# UPCNSL-ABS-PVC-TOP.net
KiCad netlist of a schematic drawn in Altium Designer
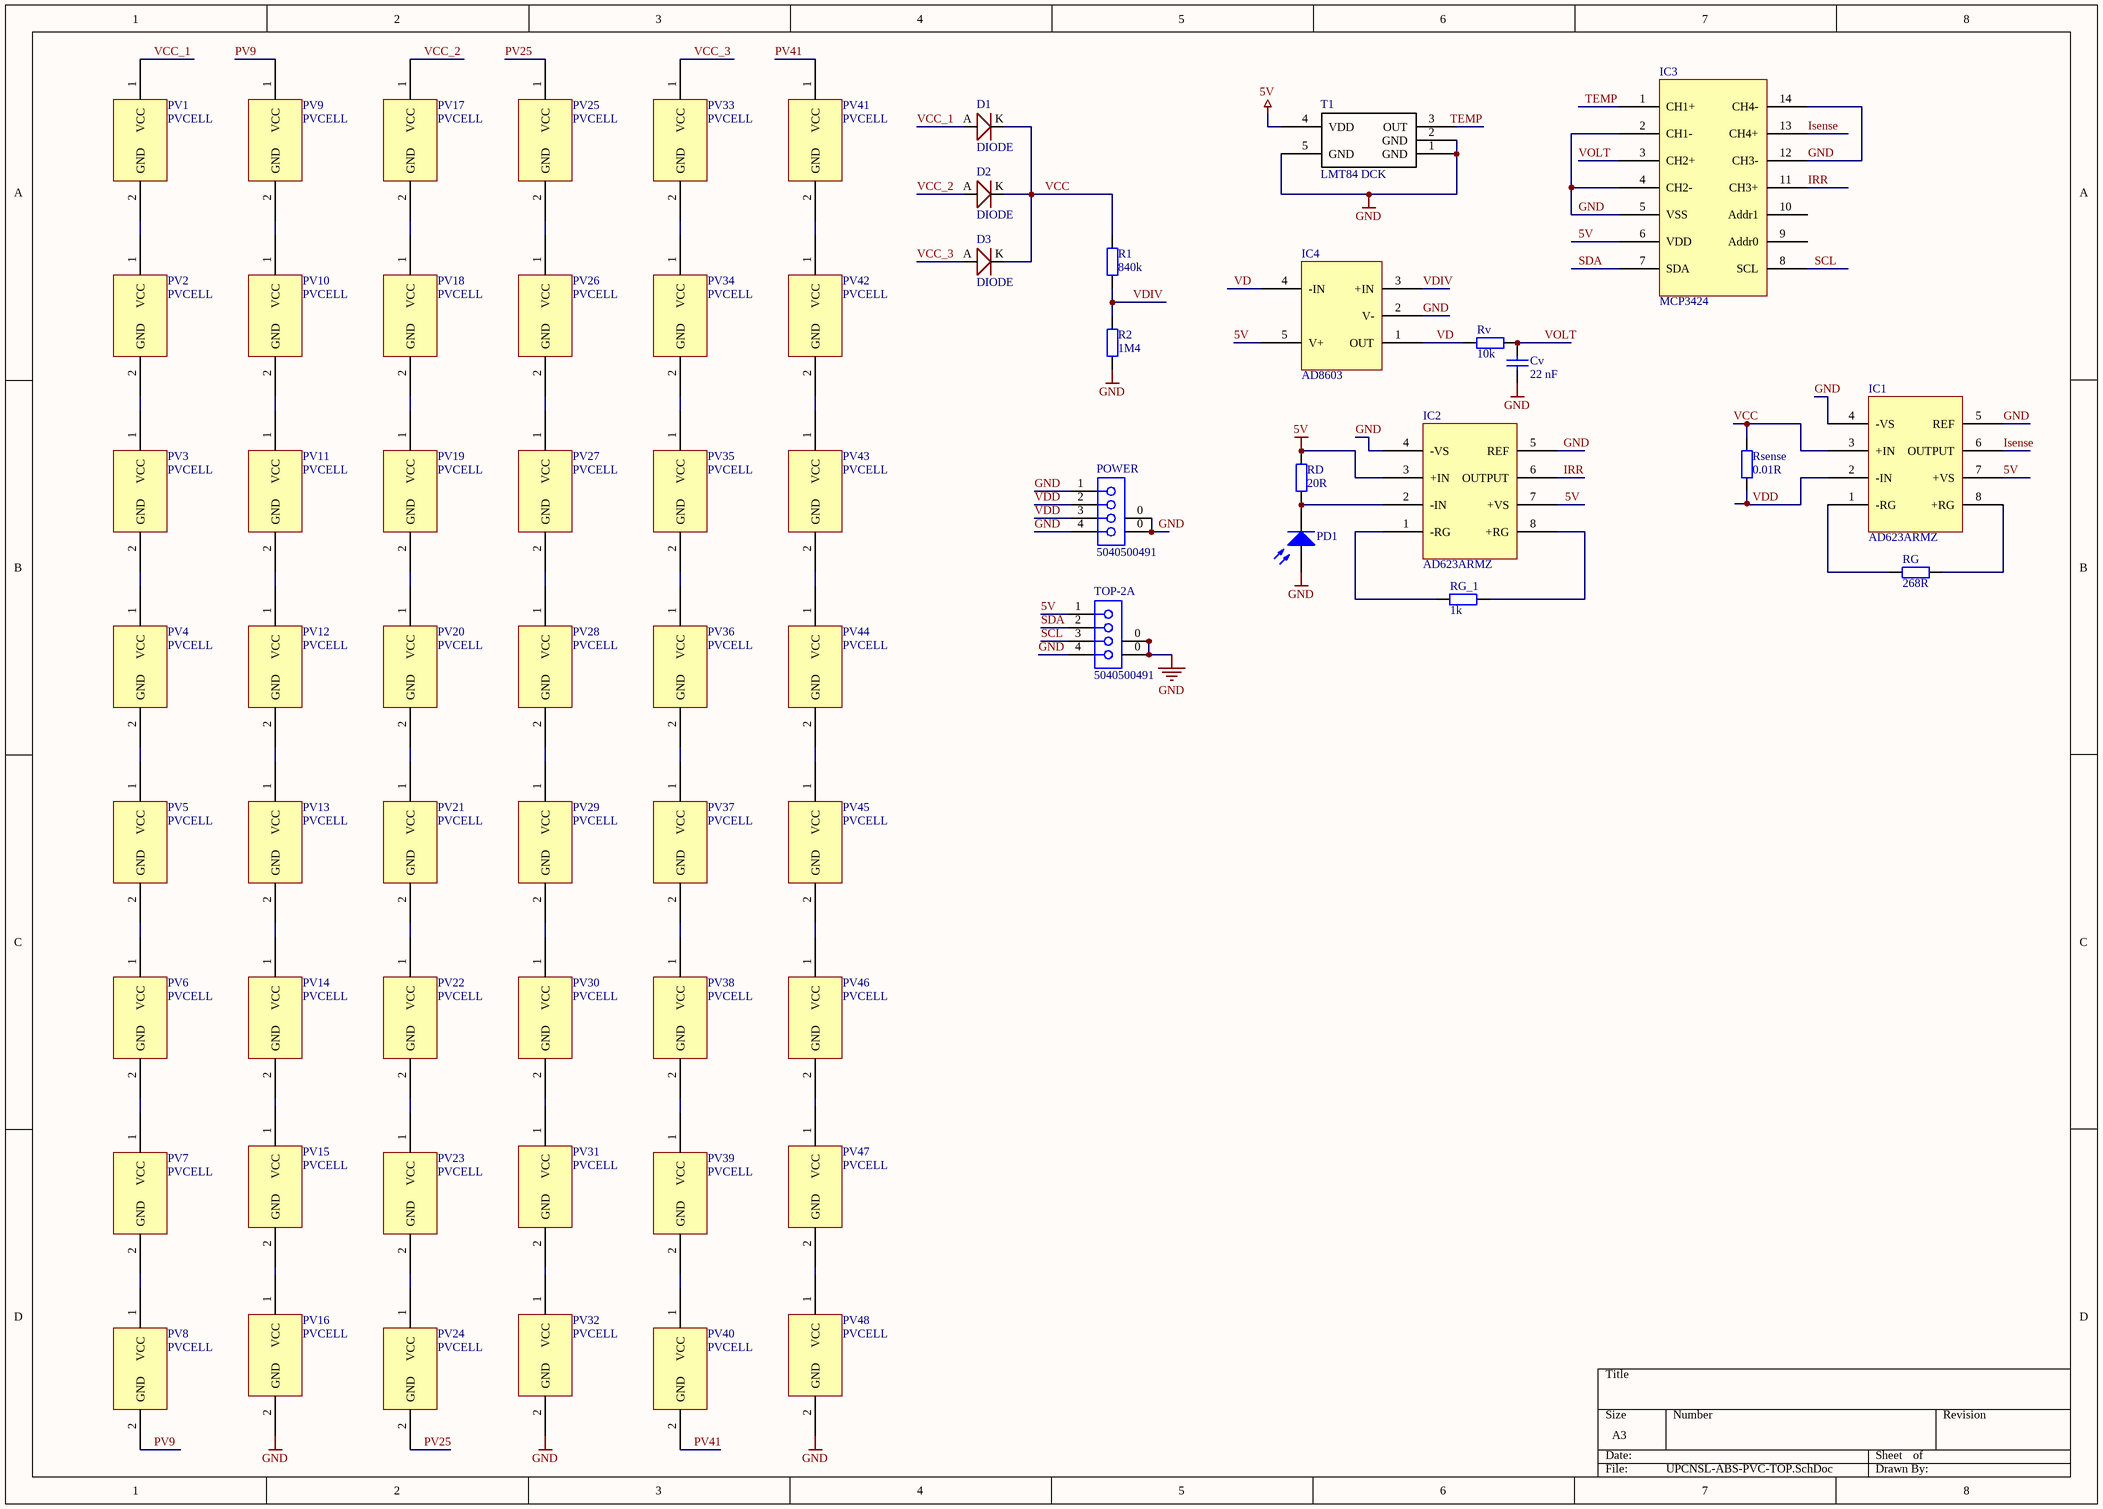
[diagram p0: UPCNSL-ABS-PVC-TOP.SchDoc]

(export (version "E")
  (design (tool "Eeschema 10.0.6"))
  (components
    (comp (ref "Cv")
      (value "22 nF")
      (footprint "CAP0603")
      (description "Capacitor")
      (fields (field (name "Comment") "CAP0603"))
      (libsource (lib "UPCNSL-ABS-FLS-ARD_v1.2") (part "CAP0603"))
    )
    (comp (ref "D1")
      (value "DIODE")
      (footprint "(Schottky diode) SODFL160X70-2N")
      (libsource (lib "UPCNSL-ABS-FLS-ARD_v1.2") (part "DIODE"))
    )
    (comp (ref "D2")
      (value "DIODE")
      (footprint "(Schottky diode) SODFL160X70-2N")
      (libsource (lib "UPCNSL-ABS-FLS-ARD_v1.2") (part "DIODE"))
    )
    (comp (ref "D3")
      (value "DIODE")
      (footprint "(Schottky diode) SODFL160X70-2N")
      (libsource (lib "UPCNSL-ABS-FLS-ARD_v1.2") (part "DIODE"))
    )
    (comp (ref "IC1")
      (value "AD623ARMZ")
      (footprint "AD623ARMZ")
      (libsource (lib "UPCNSL-ABS-FLS-PVC") (part "AD623ARMZ"))
    )
    (comp (ref "IC2")
      (value "AD623ARMZ")
      (footprint "AD623ARMZ")
      (libsource (lib "UPCNSL-ABS-FLS-PVC") (part "AD623ARMZ"))
    )
    (comp (ref "IC3")
      (value "MCP3424")
      (footprint "MCP3424")
      (description "18-Bit, Multi-Channel ΔΣ Analog-to-Digital Converter with  I2C")
      (libsource (lib "UPCNSL-ABS-FLS-PVC") (part "MCP3424"))
    )
    (comp (ref "IC4")
      (value "AD8603")
      (footprint "AD8603")
      (libsource (lib "UPCNSL-ABS-FLS-PVC") (part "AD8603"))
    )
    (comp (ref "PD1")
      (value "Photo Sen")
      (footprint "C0805")
      (description "Photosensitive Diode")
      (fields (field (name "PUBLISHER") "Altium Limited"))
      (libsource (lib "Miscellaneous Devices") (part "Photo Sen"))
    )
    (comp (ref "POWER")
      (value "5040500491")
      (footprint "5040500491")
      (libsource (lib "3CAT_Connectors") (part "MOLEX_5040500491"))
    )
    (comp (ref "PV1")
      (value "PVCELL")
      (footprint "PV CELLS")
      (description "IXYS KXOB22-12X1L-ND")
      (libsource (lib "UPCNSL-ABS-FLS-PVC") (part "PVCELLS"))
    )
    (comp (ref "PV2")
      (value "PVCELL")
      (footprint "PV CELLS")
      (description "IXYS KXOB22-12X1L-ND")
      (libsource (lib "UPCNSL-ABS-FLS-PVC") (part "PVCELLS"))
    )
    (comp (ref "PV3")
      (value "PVCELL")
      (footprint "PV CELLS")
      (description "IXYS KXOB22-12X1L-ND")
      (libsource (lib "UPCNSL-ABS-FLS-PVC") (part "PVCELLS"))
    )
    (comp (ref "PV4")
      (value "PVCELL")
      (footprint "PV CELLS")
      (description "IXYS KXOB22-12X1L-ND")
      (libsource (lib "UPCNSL-ABS-FLS-PVC") (part "PVCELLS"))
    )
    (comp (ref "PV5")
      (value "PVCELL")
      (footprint "PV CELLS")
      (description "IXYS KXOB22-12X1L-ND")
      (libsource (lib "UPCNSL-ABS-FLS-PVC") (part "PVCELLS"))
    )
    (comp (ref "PV6")
      (value "PVCELL")
      (footprint "PV CELLS")
      (description "IXYS KXOB22-12X1L-ND")
      (libsource (lib "UPCNSL-ABS-FLS-PVC") (part "PVCELLS"))
    )
    (comp (ref "PV7")
      (value "PVCELL")
      (footprint "PV CELLS")
      (description "IXYS KXOB22-12X1L-ND")
      (libsource (lib "UPCNSL-ABS-FLS-PVC") (part "PVCELLS"))
    )
    (comp (ref "PV8")
      (value "PVCELL")
      (footprint "PV CELLS")
      (description "IXYS KXOB22-12X1L-ND")
      (libsource (lib "UPCNSL-ABS-FLS-PVC") (part "PVCELLS"))
    )
    (comp (ref "PV9")
      (value "PVCELL")
      (footprint "PV CELLS")
      (description "IXYS KXOB22-12X1L-ND")
      (libsource (lib "UPCNSL-ABS-FLS-PVC") (part "PVCELLS"))
    )
    (comp (ref "PV10")
      (value "PVCELL")
      (footprint "PV CELLS")
      (description "IXYS KXOB22-12X1L-ND")
      (libsource (lib "UPCNSL-ABS-FLS-PVC") (part "PVCELLS"))
    )
    (comp (ref "PV11")
      (value "PVCELL")
      (footprint "PV CELLS")
      (description "IXYS KXOB22-12X1L-ND")
      (libsource (lib "UPCNSL-ABS-FLS-PVC") (part "PVCELLS"))
    )
    (comp (ref "PV12")
      (value "PVCELL")
      (footprint "PV CELLS")
      (description "IXYS KXOB22-12X1L-ND")
      (libsource (lib "UPCNSL-ABS-FLS-PVC") (part "PVCELLS"))
    )
    (comp (ref "PV13")
      (value "PVCELL")
      (footprint "PV CELLS")
      (description "IXYS KXOB22-12X1L-ND")
      (libsource (lib "UPCNSL-ABS-FLS-PVC") (part "PVCELLS"))
    )
    (comp (ref "PV14")
      (value "PVCELL")
      (footprint "PV CELLS")
      (description "IXYS KXOB22-12X1L-ND")
      (libsource (lib "UPCNSL-ABS-FLS-PVC") (part "PVCELLS"))
    )
    (comp (ref "PV15")
      (value "PVCELL")
      (footprint "PV CELLS")
      (description "IXYS KXOB22-12X1L-ND")
      (libsource (lib "UPCNSL-ABS-FLS-PVC") (part "PVCELLS"))
    )
    (comp (ref "PV16")
      (value "PVCELL")
      (footprint "PV CELLS")
      (description "IXYS KXOB22-12X1L-ND")
      (libsource (lib "UPCNSL-ABS-FLS-PVC") (part "PVCELLS"))
    )
    (comp (ref "PV17")
      (value "PVCELL")
      (footprint "PV CELLS")
      (description "IXYS KXOB22-12X1L-ND")
      (libsource (lib "UPCNSL-ABS-FLS-PVC") (part "PVCELLS"))
    )
    (comp (ref "PV18")
      (value "PVCELL")
      (footprint "PV CELLS")
      (description "IXYS KXOB22-12X1L-ND")
      (libsource (lib "UPCNSL-ABS-FLS-PVC") (part "PVCELLS"))
    )
    (comp (ref "PV19")
      (value "PVCELL")
      (footprint "PV CELLS")
      (description "IXYS KXOB22-12X1L-ND")
      (libsource (lib "UPCNSL-ABS-FLS-PVC") (part "PVCELLS"))
    )
    (comp (ref "PV20")
      (value "PVCELL")
      (footprint "PV CELLS")
      (description "IXYS KXOB22-12X1L-ND")
      (libsource (lib "UPCNSL-ABS-FLS-PVC") (part "PVCELLS"))
    )
    (comp (ref "PV21")
      (value "PVCELL")
      (footprint "PV CELLS")
      (description "IXYS KXOB22-12X1L-ND")
      (libsource (lib "UPCNSL-ABS-FLS-PVC") (part "PVCELLS"))
    )
    (comp (ref "PV22")
      (value "PVCELL")
      (footprint "PV CELLS")
      (description "IXYS KXOB22-12X1L-ND")
      (libsource (lib "UPCNSL-ABS-FLS-PVC") (part "PVCELLS"))
    )
    (comp (ref "PV23")
      (value "PVCELL")
      (footprint "PV CELLS")
      (description "IXYS KXOB22-12X1L-ND")
      (libsource (lib "UPCNSL-ABS-FLS-PVC") (part "PVCELLS"))
    )
    (comp (ref "PV24")
      (value "PVCELL")
      (footprint "PV CELLS")
      (description "IXYS KXOB22-12X1L-ND")
      (libsource (lib "UPCNSL-ABS-FLS-PVC") (part "PVCELLS"))
    )
    (comp (ref "PV25")
      (value "PVCELL")
      (footprint "PV CELLS")
      (description "IXYS KXOB22-12X1L-ND")
      (libsource (lib "UPCNSL-ABS-FLS-PVC") (part "PVCELLS"))
    )
    (comp (ref "PV26")
      (value "PVCELL")
      (footprint "PV CELLS")
      (description "IXYS KXOB22-12X1L-ND")
      (libsource (lib "UPCNSL-ABS-FLS-PVC") (part "PVCELLS"))
    )
    (comp (ref "PV27")
      (value "PVCELL")
      (footprint "PV CELLS")
      (description "IXYS KXOB22-12X1L-ND")
      (libsource (lib "UPCNSL-ABS-FLS-PVC") (part "PVCELLS"))
    )
    (comp (ref "PV28")
      (value "PVCELL")
      (footprint "PV CELLS")
      (description "IXYS KXOB22-12X1L-ND")
      (libsource (lib "UPCNSL-ABS-FLS-PVC") (part "PVCELLS"))
    )
    (comp (ref "PV29")
      (value "PVCELL")
      (footprint "PV CELLS")
      (description "IXYS KXOB22-12X1L-ND")
      (libsource (lib "UPCNSL-ABS-FLS-PVC") (part "PVCELLS"))
    )
    (comp (ref "PV30")
      (value "PVCELL")
      (footprint "PV CELLS")
      (description "IXYS KXOB22-12X1L-ND")
      (libsource (lib "UPCNSL-ABS-FLS-PVC") (part "PVCELLS"))
    )
    (comp (ref "PV31")
      (value "PVCELL")
      (footprint "PV CELLS")
      (description "IXYS KXOB22-12X1L-ND")
      (libsource (lib "UPCNSL-ABS-FLS-PVC") (part "PVCELLS"))
    )
    (comp (ref "PV32")
      (value "PVCELL")
      (footprint "PV CELLS")
      (description "IXYS KXOB22-12X1L-ND")
      (libsource (lib "UPCNSL-ABS-FLS-PVC") (part "PVCELLS"))
    )
    (comp (ref "PV33")
      (value "PVCELL")
      (footprint "PV CELLS")
      (description "IXYS KXOB22-12X1L-ND")
      (libsource (lib "UPCNSL-ABS-FLS-PVC") (part "PVCELLS"))
    )
    (comp (ref "PV34")
      (value "PVCELL")
      (footprint "PV CELLS")
      (description "IXYS KXOB22-12X1L-ND")
      (libsource (lib "UPCNSL-ABS-FLS-PVC") (part "PVCELLS"))
    )
    (comp (ref "PV35")
      (value "PVCELL")
      (footprint "PV CELLS")
      (description "IXYS KXOB22-12X1L-ND")
      (libsource (lib "UPCNSL-ABS-FLS-PVC") (part "PVCELLS"))
    )
    (comp (ref "PV36")
      (value "PVCELL")
      (footprint "PV CELLS")
      (description "IXYS KXOB22-12X1L-ND")
      (libsource (lib "UPCNSL-ABS-FLS-PVC") (part "PVCELLS"))
    )
    (comp (ref "PV37")
      (value "PVCELL")
      (footprint "PV CELLS")
      (description "IXYS KXOB22-12X1L-ND")
      (libsource (lib "UPCNSL-ABS-FLS-PVC") (part "PVCELLS"))
    )
    (comp (ref "PV38")
      (value "PVCELL")
      (footprint "PV CELLS")
      (description "IXYS KXOB22-12X1L-ND")
      (libsource (lib "UPCNSL-ABS-FLS-PVC") (part "PVCELLS"))
    )
    (comp (ref "PV39")
      (value "PVCELL")
      (footprint "PV CELLS")
      (description "IXYS KXOB22-12X1L-ND")
      (libsource (lib "UPCNSL-ABS-FLS-PVC") (part "PVCELLS"))
    )
    (comp (ref "PV40")
      (value "PVCELL")
      (footprint "PV CELLS")
      (description "IXYS KXOB22-12X1L-ND")
      (libsource (lib "UPCNSL-ABS-FLS-PVC") (part "PVCELLS"))
    )
    (comp (ref "PV41")
      (value "PVCELL")
      (footprint "PV CELLS")
      (description "IXYS KXOB22-12X1L-ND")
      (libsource (lib "UPCNSL-ABS-FLS-PVC") (part "PVCELLS"))
    )
    (comp (ref "PV42")
      (value "PVCELL")
      (footprint "PV CELLS")
      (description "IXYS KXOB22-12X1L-ND")
      (libsource (lib "UPCNSL-ABS-FLS-PVC") (part "PVCELLS"))
    )
    (comp (ref "PV43")
      (value "PVCELL")
      (footprint "PV CELLS")
      (description "IXYS KXOB22-12X1L-ND")
      (libsource (lib "UPCNSL-ABS-FLS-PVC") (part "PVCELLS"))
    )
    (comp (ref "PV44")
      (value "PVCELL")
      (footprint "PV CELLS")
      (description "IXYS KXOB22-12X1L-ND")
      (libsource (lib "UPCNSL-ABS-FLS-PVC") (part "PVCELLS"))
    )
    (comp (ref "PV45")
      (value "PVCELL")
      (footprint "PV CELLS")
      (description "IXYS KXOB22-12X1L-ND")
      (libsource (lib "UPCNSL-ABS-FLS-PVC") (part "PVCELLS"))
    )
    (comp (ref "PV46")
      (value "PVCELL")
      (footprint "PV CELLS")
      (description "IXYS KXOB22-12X1L-ND")
      (libsource (lib "UPCNSL-ABS-FLS-PVC") (part "PVCELLS"))
    )
    (comp (ref "PV47")
      (value "PVCELL")
      (footprint "PV CELLS")
      (description "IXYS KXOB22-12X1L-ND")
      (libsource (lib "UPCNSL-ABS-FLS-PVC") (part "PVCELLS"))
    )
    (comp (ref "PV48")
      (value "PVCELL")
      (footprint "PV CELLS")
      (description "IXYS KXOB22-12X1L-ND")
      (libsource (lib "UPCNSL-ABS-FLS-PVC") (part "PVCELLS"))
    )
    (comp (ref "R1")
      (value "840k")
      (footprint "RES0603")
      (description "Resistor")
      (fields (field (name "Comment") "RES0603"))
      (libsource (lib "UPCNSL-ABS-FLS-ARD_v1.2") (part "RES0603"))
    )
    (comp (ref "R2")
      (value "1M4")
      (footprint "RES0603")
      (description "Resistor")
      (fields (field (name "Comment") "RES0603"))
      (libsource (lib "UPCNSL-ABS-FLS-ARD_v1.2") (part "RES0603"))
    )
    (comp (ref "RD")
      (value "20R")
      (footprint "RES0603")
      (description "Resistor")
      (fields (field (name "Comment") "RES0603"))
      (libsource (lib "UPCNSL-ABS-FLS-ARD_v1.2") (part "RES0603"))
    )
    (comp (ref "RG")
      (value "268R")
      (footprint "RES0603")
      (description "Resistor")
      (fields (field (name "Comment") "RES0603"))
      (libsource (lib "") (part "RES0603_1"))
    )
    (comp (ref "RG_1")
      (value "1k")
      (footprint "RES0603")
      (description "Resistor")
      (fields (field (name "Comment") "RES0603"))
      (libsource (lib "") (part "RES0603_1"))
    )
    (comp (ref "Rsense")
      (value "0.01R")
      (footprint "RES0603")
      (description "Resistor")
      (fields (field (name "Comment") "RES0603"))
      (libsource (lib "UPCNSL-ABS-FLS-ARD_v1.2") (part "RES0603"))
    )
    (comp (ref "Rv")
      (value "10k")
      (footprint "RES0603")
      (description "Resistor")
      (fields (field (name "Comment") "RES0603"))
      (libsource (lib "") (part "RES0603_1"))
    )
    (comp (ref "T1")
      (value "LMT84 DCK")
      (footprint "DCK/SOT65P210X110-5N")
      (libsource (lib "UPCNSL-ABS-FLS-PVC") (part "LMT84 DCK"))
    )
    (comp (ref "TOP-2A")
      (value "5040500491")
      (footprint "5040500491")
      (libsource (lib "3CAT_Connectors") (part "MOLEX_5040500491"))
    )
  )
  (nets
    (net (code "1") (name "/IRR") (class "Default")
      (node (ref "IC2") (pin "6") (pinfunction "OUTPUT_6") (pintype "passive"))
      (node (ref "IC3") (pin "11") (pinfunction "CH3+_11") (pintype "passive"))
    )
    (net (code "2") (name "/Isense") (class "Default")
      (node (ref "IC1") (pin "6") (pinfunction "OUTPUT_6") (pintype "passive"))
      (node (ref "IC3") (pin "13") (pinfunction "CH4+_13") (pintype "passive"))
    )
    (net (code "3") (name "/PV9") (class "Default")
      (node (ref "PV8") (pin "2") (pinfunction "GND_2") (pintype "passive"))
      (node (ref "PV9") (pin "1") (pinfunction "VCC_1") (pintype "passive"))
    )
    (net (code "4") (name "/PV25") (class "Default")
      (node (ref "PV24") (pin "2") (pinfunction "GND_2") (pintype "passive"))
      (node (ref "PV25") (pin "1") (pinfunction "VCC_1") (pintype "passive"))
    )
    (net (code "5") (name "/PV41") (class "Default")
      (node (ref "PV40") (pin "2") (pinfunction "GND_2") (pintype "passive"))
      (node (ref "PV41") (pin "1") (pinfunction "VCC_1") (pintype "passive"))
    )
    (net (code "6") (name "/SCL") (class "Default")
      (node (ref "IC3") (pin "8") (pinfunction "SCL_8") (pintype "passive"))
      (node (ref "TOP-2A") (pin "3") (pinfunction "3_3") (pintype "passive"))
    )
    (net (code "7") (name "/SDA") (class "Default")
      (node (ref "IC3") (pin "7") (pinfunction "SDA_7") (pintype "passive"))
      (node (ref "TOP-2A") (pin "2") (pinfunction "2_2") (pintype "passive"))
    )
    (net (code "8") (name "/TEMP") (class "Default")
      (node (ref "IC3") (pin "1") (pinfunction "CH1+_1") (pintype "passive"))
    )
    (net (code "9") (name "/VCC") (class "Default")
      (node (ref "D1") (pin "K") (pinfunction "K_K") (pintype "passive"))
      (node (ref "D2") (pin "K") (pinfunction "K_K") (pintype "passive"))
      (node (ref "D3") (pin "K") (pinfunction "K_K") (pintype "passive"))
      (node (ref "IC1") (pin "3") (pinfunction "+IN_3") (pintype "passive"))
      (node (ref "R1") (pin "2") (pinfunction "2_2") (pintype "passive"))
      (node (ref "Rsense") (pin "2") (pinfunction "2_2") (pintype "passive"))
    )
    (net (code "10") (name "/VCC_1") (class "Default")
      (node (ref "D1") (pin "A") (pinfunction "A_A") (pintype "passive"))
      (node (ref "PV1") (pin "1") (pinfunction "VCC_1") (pintype "passive"))
    )
    (net (code "11") (name "/VCC_2") (class "Default")
      (node (ref "D2") (pin "A") (pinfunction "A_A") (pintype "passive"))
      (node (ref "PV17") (pin "1") (pinfunction "VCC_1") (pintype "passive"))
    )
    (net (code "12") (name "/VCC_3") (class "Default")
      (node (ref "D3") (pin "A") (pinfunction "A_A") (pintype "passive"))
      (node (ref "PV33") (pin "1") (pinfunction "VCC_1") (pintype "passive"))
    )
    (net (code "13") (name "/VD") (class "Default")
      (node (ref "IC4") (pin "1") (pinfunction "OUT_1") (pintype "passive"))
      (node (ref "IC4") (pin "4") (pinfunction "-IN_4") (pintype "passive"))
      (node (ref "Rv") (pin "1") (pinfunction "1_1") (pintype "passive"))
    )
    (net (code "14") (name "/VDD") (class "Default")
      (node (ref "IC1") (pin "2") (pinfunction "-IN_2") (pintype "passive"))
      (node (ref "POWER") (pin "2") (pinfunction "2_2") (pintype "passive"))
      (node (ref "POWER") (pin "3") (pinfunction "3_3") (pintype "passive"))
      (node (ref "Rsense") (pin "1") (pinfunction "1_1") (pintype "passive"))
    )
    (net (code "15") (name "/VDIV") (class "Default")
      (node (ref "IC4") (pin "3") (pinfunction "+IN_3") (pintype "passive"))
      (node (ref "R1") (pin "1") (pinfunction "1_1") (pintype "passive"))
      (node (ref "R2") (pin "2") (pinfunction "2_2") (pintype "passive"))
    )
    (net (code "16") (name "/VOLT") (class "Default")
      (node (ref "Cv") (pin "2") (pinfunction "2_2") (pintype "passive"))
      (node (ref "IC3") (pin "3") (pinfunction "CH2+_3") (pintype "passive"))
      (node (ref "Rv") (pin "2") (pinfunction "2_2") (pintype "passive"))
    )
    (net (code "17") (name "5V") (class "Default")
      (node (ref "IC1") (pin "7") (pinfunction "+VS_7") (pintype "passive"))
      (node (ref "IC2") (pin "3") (pinfunction "+IN_3") (pintype "passive"))
      (node (ref "IC2") (pin "7") (pinfunction "+VS_7") (pintype "passive"))
      (node (ref "IC3") (pin "6") (pinfunction "VDD_6") (pintype "passive"))
      (node (ref "IC4") (pin "5") (pinfunction "V+_5") (pintype "passive"))
      (node (ref "RD") (pin "2") (pinfunction "2_2") (pintype "passive"))
      (node (ref "T1") (pin "4") (pinfunction "VDD_4") (pintype "passive"))
      (node (ref "TOP-2A") (pin "1") (pinfunction "1_1") (pintype "passive"))
    )
    (net (code "18") (name "GND") (class "Default")
      (node (ref "Cv") (pin "1") (pinfunction "1_1") (pintype "passive"))
      (node (ref "IC1") (pin "4") (pinfunction "-VS_4") (pintype "passive"))
      (node (ref "IC1") (pin "5") (pinfunction "REF_5") (pintype "passive"))
      (node (ref "IC2") (pin "4") (pinfunction "-VS_4") (pintype "passive"))
      (node (ref "IC2") (pin "5") (pinfunction "REF_5") (pintype "passive"))
      (node (ref "IC3") (pin "12") (pinfunction "CH3-_12") (pintype "passive"))
      (node (ref "IC3") (pin "14") (pinfunction "CH4-_14") (pintype "passive"))
      (node (ref "IC3") (pin "2") (pinfunction "CH1-_2") (pintype "passive"))
      (node (ref "IC3") (pin "4") (pinfunction "CH2-_4") (pintype "passive"))
      (node (ref "IC3") (pin "5") (pinfunction "VSS_5") (pintype "passive"))
      (node (ref "IC4") (pin "2") (pinfunction "V-_2") (pintype "passive"))
      (node (ref "PD1") (pin "1") (pinfunction "A_1") (pintype "passive"))
      (node (ref "POWER") (pin "0") (pinfunction "MH1_0") (pintype "passive"))
      (node (ref "POWER") (pin "1") (pinfunction "1_1") (pintype "passive"))
      (node (ref "POWER") (pin "4") (pinfunction "4_4") (pintype "passive"))
      (node (ref "PV16") (pin "2") (pinfunction "GND_2") (pintype "passive"))
      (node (ref "PV32") (pin "2") (pinfunction "GND_2") (pintype "passive"))
      (node (ref "PV48") (pin "2") (pinfunction "GND_2") (pintype "passive"))
      (node (ref "R2") (pin "1") (pinfunction "1_1") (pintype "passive"))
      (node (ref "T1") (pin "1") (pinfunction "GND_1") (pintype "passive"))
      (node (ref "T1") (pin "2") (pinfunction "GND_2") (pintype "passive"))
      (node (ref "T1") (pin "5") (pinfunction "GND_5") (pintype "passive"))
      (node (ref "TOP-2A") (pin "0") (pinfunction "MH2_0") (pintype "passive"))
      (node (ref "TOP-2A") (pin "4") (pinfunction "4_4") (pintype "passive"))
    )
    (net (code "19") (name "Net-(IC1-+RG)") (class "Default")
      (node (ref "IC1") (pin "8") (pinfunction "+RG_8") (pintype "passive"))
      (node (ref "RG") (pin "2") (pinfunction "2_2") (pintype "passive"))
    )
    (net (code "20") (name "Net-(IC1--RG)") (class "Default")
      (node (ref "IC1") (pin "1") (pinfunction "-RG_1") (pintype "passive"))
      (node (ref "RG") (pin "1") (pinfunction "1_1") (pintype "passive"))
    )
    (net (code "21") (name "Net-(IC2-+RG)") (class "Default")
      (node (ref "IC2") (pin "8") (pinfunction "+RG_8") (pintype "passive"))
      (node (ref "RG_1") (pin "2") (pinfunction "2_2") (pintype "passive"))
    )
    (net (code "22") (name "Net-(IC2--IN)") (class "Default")
      (node (ref "IC2") (pin "2") (pinfunction "-IN_2") (pintype "passive"))
      (node (ref "PD1") (pin "2") (pinfunction "K_2") (pintype "passive"))
      (node (ref "RD") (pin "1") (pinfunction "1_1") (pintype "passive"))
    )
    (net (code "23") (name "Net-(IC2--RG)") (class "Default")
      (node (ref "IC2") (pin "1") (pinfunction "-RG_1") (pintype "passive"))
      (node (ref "RG_1") (pin "1") (pinfunction "1_1") (pintype "passive"))
    )
    (net (code "24") (name "Net-(PV1-GND)") (class "Default")
      (node (ref "PV1") (pin "2") (pinfunction "GND_2") (pintype "passive"))
      (node (ref "PV2") (pin "1") (pinfunction "VCC_1") (pintype "passive"))
    )
    (net (code "25") (name "Net-(PV2-GND)") (class "Default")
      (node (ref "PV2") (pin "2") (pinfunction "GND_2") (pintype "passive"))
      (node (ref "PV3") (pin "1") (pinfunction "VCC_1") (pintype "passive"))
    )
    (net (code "26") (name "Net-(PV3-GND)") (class "Default")
      (node (ref "PV3") (pin "2") (pinfunction "GND_2") (pintype "passive"))
      (node (ref "PV4") (pin "1") (pinfunction "VCC_1") (pintype "passive"))
    )
    (net (code "27") (name "Net-(PV4-GND)") (class "Default")
      (node (ref "PV4") (pin "2") (pinfunction "GND_2") (pintype "passive"))
      (node (ref "PV5") (pin "1") (pinfunction "VCC_1") (pintype "passive"))
    )
    (net (code "28") (name "Net-(PV5-GND)") (class "Default")
      (node (ref "PV5") (pin "2") (pinfunction "GND_2") (pintype "passive"))
      (node (ref "PV6") (pin "1") (pinfunction "VCC_1") (pintype "passive"))
    )
    (net (code "29") (name "Net-(PV6-GND)") (class "Default")
      (node (ref "PV6") (pin "2") (pinfunction "GND_2") (pintype "passive"))
      (node (ref "PV7") (pin "1") (pinfunction "VCC_1") (pintype "passive"))
    )
    (net (code "30") (name "Net-(PV7-GND)") (class "Default")
      (node (ref "PV7") (pin "2") (pinfunction "GND_2") (pintype "passive"))
      (node (ref "PV8") (pin "1") (pinfunction "VCC_1") (pintype "passive"))
    )
    (net (code "31") (name "Net-(PV10-GND)") (class "Default")
      (node (ref "PV10") (pin "2") (pinfunction "GND_2") (pintype "passive"))
      (node (ref "PV11") (pin "1") (pinfunction "VCC_1") (pintype "passive"))
    )
    (net (code "32") (name "Net-(PV10-VCC)") (class "Default")
      (node (ref "PV10") (pin "1") (pinfunction "VCC_1") (pintype "passive"))
      (node (ref "PV9") (pin "2") (pinfunction "GND_2") (pintype "passive"))
    )
    (net (code "33") (name "Net-(PV11-GND)") (class "Default")
      (node (ref "PV11") (pin "2") (pinfunction "GND_2") (pintype "passive"))
      (node (ref "PV12") (pin "1") (pinfunction "VCC_1") (pintype "passive"))
    )
    (net (code "34") (name "Net-(PV12-GND)") (class "Default")
      (node (ref "PV12") (pin "2") (pinfunction "GND_2") (pintype "passive"))
      (node (ref "PV13") (pin "1") (pinfunction "VCC_1") (pintype "passive"))
    )
    (net (code "35") (name "Net-(PV13-GND)") (class "Default")
      (node (ref "PV13") (pin "2") (pinfunction "GND_2") (pintype "passive"))
      (node (ref "PV14") (pin "1") (pinfunction "VCC_1") (pintype "passive"))
    )
    (net (code "36") (name "Net-(PV14-GND)") (class "Default")
      (node (ref "PV14") (pin "2") (pinfunction "GND_2") (pintype "passive"))
      (node (ref "PV15") (pin "1") (pinfunction "VCC_1") (pintype "passive"))
    )
    (net (code "37") (name "Net-(PV15-GND)") (class "Default")
      (node (ref "PV15") (pin "2") (pinfunction "GND_2") (pintype "passive"))
      (node (ref "PV16") (pin "1") (pinfunction "VCC_1") (pintype "passive"))
    )
    (net (code "38") (name "Net-(PV17-GND)") (class "Default")
      (node (ref "PV17") (pin "2") (pinfunction "GND_2") (pintype "passive"))
      (node (ref "PV18") (pin "1") (pinfunction "VCC_1") (pintype "passive"))
    )
    (net (code "39") (name "Net-(PV18-GND)") (class "Default")
      (node (ref "PV18") (pin "2") (pinfunction "GND_2") (pintype "passive"))
      (node (ref "PV19") (pin "1") (pinfunction "VCC_1") (pintype "passive"))
    )
    (net (code "40") (name "Net-(PV19-GND)") (class "Default")
      (node (ref "PV19") (pin "2") (pinfunction "GND_2") (pintype "passive"))
      (node (ref "PV20") (pin "1") (pinfunction "VCC_1") (pintype "passive"))
    )
    (net (code "41") (name "Net-(PV20-GND)") (class "Default")
      (node (ref "PV20") (pin "2") (pinfunction "GND_2") (pintype "passive"))
      (node (ref "PV21") (pin "1") (pinfunction "VCC_1") (pintype "passive"))
    )
    (net (code "42") (name "Net-(PV21-GND)") (class "Default")
      (node (ref "PV21") (pin "2") (pinfunction "GND_2") (pintype "passive"))
      (node (ref "PV22") (pin "1") (pinfunction "VCC_1") (pintype "passive"))
    )
    (net (code "43") (name "Net-(PV22-GND)") (class "Default")
      (node (ref "PV22") (pin "2") (pinfunction "GND_2") (pintype "passive"))
      (node (ref "PV23") (pin "1") (pinfunction "VCC_1") (pintype "passive"))
    )
    (net (code "44") (name "Net-(PV23-GND)") (class "Default")
      (node (ref "PV23") (pin "2") (pinfunction "GND_2") (pintype "passive"))
      (node (ref "PV24") (pin "1") (pinfunction "VCC_1") (pintype "passive"))
    )
    (net (code "45") (name "Net-(PV25-GND)") (class "Default")
      (node (ref "PV25") (pin "2") (pinfunction "GND_2") (pintype "passive"))
      (node (ref "PV26") (pin "1") (pinfunction "VCC_1") (pintype "passive"))
    )
    (net (code "46") (name "Net-(PV26-GND)") (class "Default")
      (node (ref "PV26") (pin "2") (pinfunction "GND_2") (pintype "passive"))
      (node (ref "PV27") (pin "1") (pinfunction "VCC_1") (pintype "passive"))
    )
    (net (code "47") (name "Net-(PV27-GND)") (class "Default")
      (node (ref "PV27") (pin "2") (pinfunction "GND_2") (pintype "passive"))
      (node (ref "PV28") (pin "1") (pinfunction "VCC_1") (pintype "passive"))
    )
    (net (code "48") (name "Net-(PV28-GND)") (class "Default")
      (node (ref "PV28") (pin "2") (pinfunction "GND_2") (pintype "passive"))
      (node (ref "PV29") (pin "1") (pinfunction "VCC_1") (pintype "passive"))
    )
    (net (code "49") (name "Net-(PV29-GND)") (class "Default")
      (node (ref "PV29") (pin "2") (pinfunction "GND_2") (pintype "passive"))
      (node (ref "PV30") (pin "1") (pinfunction "VCC_1") (pintype "passive"))
    )
    (net (code "50") (name "Net-(PV30-GND)") (class "Default")
      (node (ref "PV30") (pin "2") (pinfunction "GND_2") (pintype "passive"))
      (node (ref "PV31") (pin "1") (pinfunction "VCC_1") (pintype "passive"))
    )
    (net (code "51") (name "Net-(PV31-GND)") (class "Default")
      (node (ref "PV31") (pin "2") (pinfunction "GND_2") (pintype "passive"))
      (node (ref "PV32") (pin "1") (pinfunction "VCC_1") (pintype "passive"))
    )
    (net (code "52") (name "Net-(PV33-GND)") (class "Default")
      (node (ref "PV33") (pin "2") (pinfunction "GND_2") (pintype "passive"))
      (node (ref "PV34") (pin "1") (pinfunction "VCC_1") (pintype "passive"))
    )
    (net (code "53") (name "Net-(PV34-GND)") (class "Default")
      (node (ref "PV34") (pin "2") (pinfunction "GND_2") (pintype "passive"))
      (node (ref "PV35") (pin "1") (pinfunction "VCC_1") (pintype "passive"))
    )
    (net (code "54") (name "Net-(PV35-GND)") (class "Default")
      (node (ref "PV35") (pin "2") (pinfunction "GND_2") (pintype "passive"))
      (node (ref "PV36") (pin "1") (pinfunction "VCC_1") (pintype "passive"))
    )
    (net (code "55") (name "Net-(PV36-GND)") (class "Default")
      (node (ref "PV36") (pin "2") (pinfunction "GND_2") (pintype "passive"))
      (node (ref "PV37") (pin "1") (pinfunction "VCC_1") (pintype "passive"))
    )
    (net (code "56") (name "Net-(PV37-GND)") (class "Default")
      (node (ref "PV37") (pin "2") (pinfunction "GND_2") (pintype "passive"))
      (node (ref "PV38") (pin "1") (pinfunction "VCC_1") (pintype "passive"))
    )
    (net (code "57") (name "Net-(PV38-GND)") (class "Default")
      (node (ref "PV38") (pin "2") (pinfunction "GND_2") (pintype "passive"))
      (node (ref "PV39") (pin "1") (pinfunction "VCC_1") (pintype "passive"))
    )
    (net (code "58") (name "Net-(PV39-GND)") (class "Default")
      (node (ref "PV39") (pin "2") (pinfunction "GND_2") (pintype "passive"))
      (node (ref "PV40") (pin "1") (pinfunction "VCC_1") (pintype "passive"))
    )
    (net (code "59") (name "Net-(PV41-GND)") (class "Default")
      (node (ref "PV41") (pin "2") (pinfunction "GND_2") (pintype "passive"))
      (node (ref "PV42") (pin "1") (pinfunction "VCC_1") (pintype "passive"))
    )
    (net (code "60") (name "Net-(PV42-GND)") (class "Default")
      (node (ref "PV42") (pin "2") (pinfunction "GND_2") (pintype "passive"))
      (node (ref "PV43") (pin "1") (pinfunction "VCC_1") (pintype "passive"))
    )
    (net (code "61") (name "Net-(PV43-GND)") (class "Default")
      (node (ref "PV43") (pin "2") (pinfunction "GND_2") (pintype "passive"))
      (node (ref "PV44") (pin "1") (pinfunction "VCC_1") (pintype "passive"))
    )
    (net (code "62") (name "Net-(PV44-GND)") (class "Default")
      (node (ref "PV44") (pin "2") (pinfunction "GND_2") (pintype "passive"))
      (node (ref "PV45") (pin "1") (pinfunction "VCC_1") (pintype "passive"))
    )
    (net (code "63") (name "Net-(PV45-GND)") (class "Default")
      (node (ref "PV45") (pin "2") (pinfunction "GND_2") (pintype "passive"))
      (node (ref "PV46") (pin "1") (pinfunction "VCC_1") (pintype "passive"))
    )
    (net (code "64") (name "Net-(PV46-GND)") (class "Default")
      (node (ref "PV46") (pin "2") (pinfunction "GND_2") (pintype "passive"))
      (node (ref "PV47") (pin "1") (pinfunction "VCC_1") (pintype "passive"))
    )
    (net (code "65") (name "Net-(PV47-GND)") (class "Default")
      (node (ref "PV47") (pin "2") (pinfunction "GND_2") (pintype "passive"))
      (node (ref "PV48") (pin "1") (pinfunction "VCC_1") (pintype "passive"))
    )
    (net (code "66") (name "unconnected-(IC3-Addr0-Pad9)") (class "Default")
      (node (ref "IC3") (pin "9") (pinfunction "Addr0_9") (pintype "passive"))
    )
    (net (code "67") (name "unconnected-(IC3-Addr1-Pad10)") (class "Default")
      (node (ref "IC3") (pin "10") (pinfunction "Addr1_10") (pintype "passive"))
    )
    (net (code "68") (name "unconnected-(T1-OUT-Pad3)") (class "Default")
      (node (ref "T1") (pin "3") (pinfunction "OUT_3") (pintype "passive"))
    )
  )
)
